# Microcontroller_Power___RF.net
KiCad netlist of a schematic drawn in Altium Designer
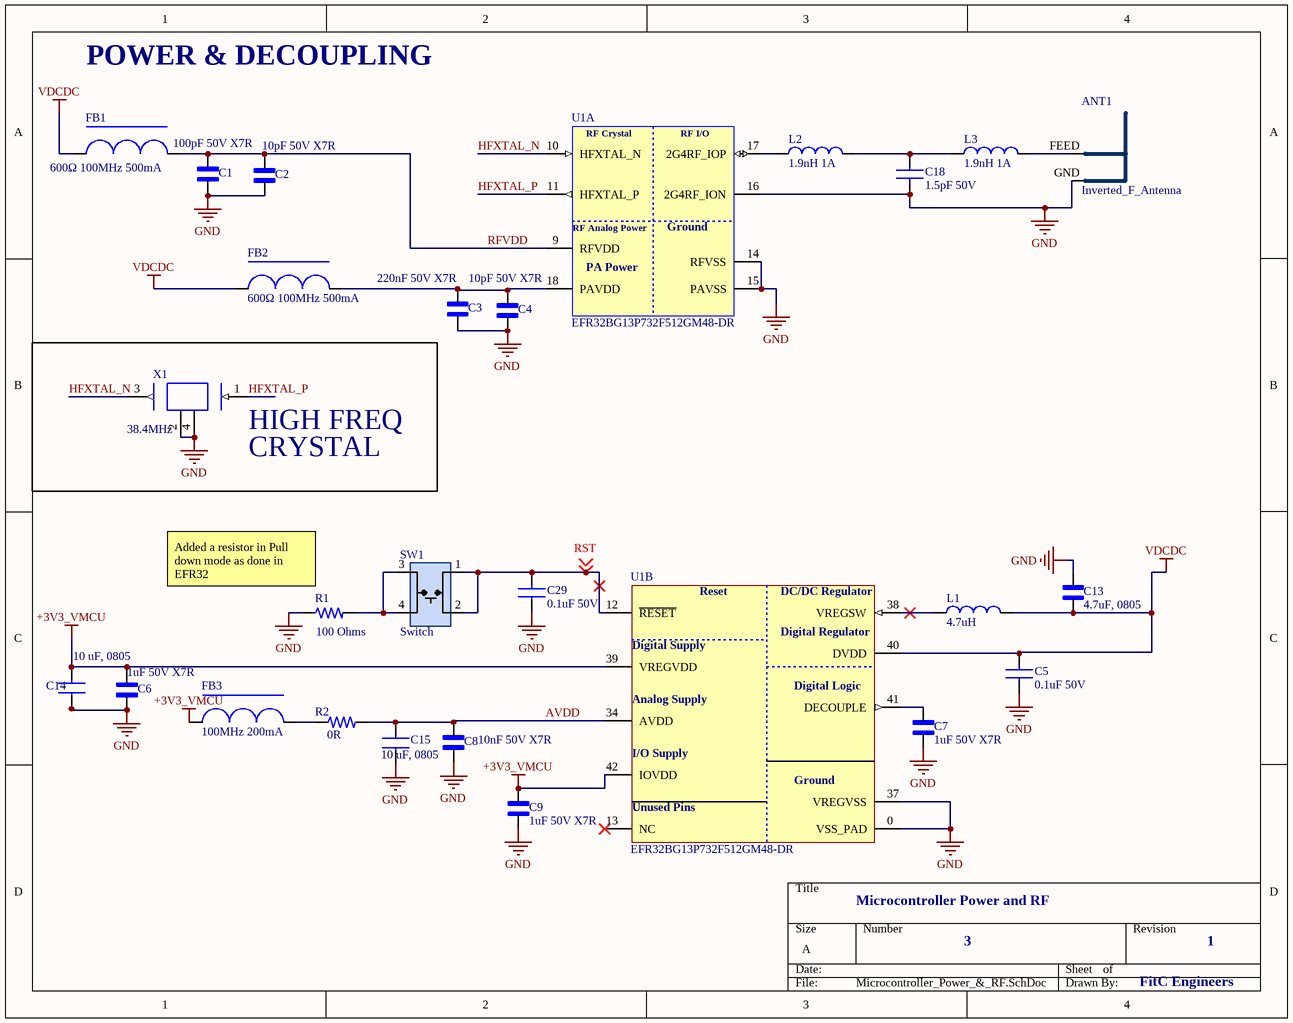
[diagram p0: Microcontroller_Power_&_RF.SchDoc]

(export (version "E")
  (design (tool "Eeschema 10.0.6"))
  (components
    (comp (ref "ANT1")
      (value "Inverted_F_Antenna")
      (footprint "INV_F_Antenna")
      (libsource (lib "LP_Project_Parts") (part "Inv_F_Antenna"))
    )
    (comp (ref "C1")
      (value "100pF 50V X7R")
      (footprint "CAP_0603_1MM")
      (description "100pF ±10% 50V 0603")
      (fields
        (field (name "MANUFACTURER") "Samsung")
        (field (name "MANUFACTURER PART NUMBER") "CL10B101KB8NFNC")
      )
      (libsource (lib "LP_Project_Parts") (part "CL10B101KB8NFNC"))
    )
    (comp (ref "C2")
      (value "10pF 50V X7R")
      (footprint "CAP_0603_1MM")
      (description "0603 10 pF 50 V ±10 % Tolerance X7R Surface Mount Multilayer Ceramic Capacitor")
      (fields
        (field (name "MANUFACTURER") "Kyocera AVX")
        (field (name "MANUFACTURER PART NUMBER") "06035C100KAT2A")
      )
      (libsource (lib "LP_Project_Parts") (part "06035C100KAT2A"))
    )
    (comp (ref "C3")
      (value "220nF 50V X7R")
      (footprint "CAP_0603_1MM")
      (description "C Series 0603 0.22 uF 50 V ±10 % Tolerance X7R SMT Multilayer Ceramic Capacitor")
      (fields
        (field (name "MANUFACTURER") "TDK")
        (field (name "MANUFACTURER PART NUMBER") "C1608X7R1H224K080AB")
      )
      (libsource (lib "LP_Project_Parts") (part "C1608X7R1H224K080AB"))
    )
    (comp (ref "C4")
      (value "10pF 50V X7R")
      (footprint "CAP_0603_1MM")
      (description "0603 10 pF 50 V ±10 % Tolerance X7R Surface Mount Multilayer Ceramic Capacitor")
      (fields
        (field (name "MANUFACTURER") "Kyocera AVX")
        (field (name "MANUFACTURER PART NUMBER") "06035C100KAT2A")
      )
      (libsource (lib "LP_Project_Parts") (part "06035C100KAT2A"))
    )
    (comp (ref "C5")
      (value "0.1uF 50V")
      (footprint "CAP_0603_1MM")
      (description "Cap Ceramic 0.1uF 50V X7R 10% Pad SMD 0603 Flexible Termination 125C Automotive Medical Bag")
      (fields
        (field (name "MANUFACTURER") "KEMET")
        (field (name "MANUFACTURER PART NUMBER") "C0603X104K5RAC3121")
      )
      (libsource (lib "LP_Project_Parts") (part "C0603X104K5RAC3121"))
    )
    (comp (ref "C6")
      (value "1uF 50V X7R")
      (footprint "CAP_0603_1MM")
      (description "0603 1uF Multilayer Ceramic Capacitors 0603 50V X7R 105 10% TOL")
      (fields
        (field (name "MANUFACTURER") "Kyocera AVX")
        (field (name "MANUFACTURER PART NUMBER") "06035C105KAT2A")
      )
      (libsource (lib "LP_Project_Parts") (part "06035C105KAT2A"))
    )
    (comp (ref "C7")
      (value "1uF 50V X7R")
      (footprint "CAP_0603_1MM")
      (description "0603 1uF Multilayer Ceramic Capacitors 0603 50V X7R 105 10% TOL")
      (fields
        (field (name "MANUFACTURER") "Kyocera AVX")
        (field (name "MANUFACTURER PART NUMBER") "06035C105KAT2A")
      )
      (libsource (lib "LP_Project_Parts") (part "06035C105KAT2A"))
    )
    (comp (ref "C8")
      (value "10nF 50V X7R")
      (footprint "CAP_0603_1MM")
      (description "Capacitor Ceramic 0.01uF 10% 50V 2-Pin Surface Mount T/R")
      (fields
        (field (name "MANUFACTURER") "Samsung")
        (field (name "MANUFACTURER PART NUMBER") "CL10B103KB8WPJC")
      )
      (libsource (lib "LP_Project_Parts") (part "CL10B103KB8WPJC"))
    )
    (comp (ref "C9")
      (value "1uF 50V X7R")
      (footprint "CAP_0603_1MM")
      (description "0603 1uF Multilayer Ceramic Capacitors 0603 50V X7R 105 10% TOL")
      (fields
        (field (name "MANUFACTURER") "Kyocera AVX")
        (field (name "MANUFACTURER PART NUMBER") "06035C105KAT2A")
      )
      (libsource (lib "LP_Project_Parts") (part "06035C105KAT2A"))
    )
    (comp (ref "C13")
      (value "4.7uF, 0805")
      (footprint "CAP_0805_2012X14")
      (description "0805 4.7 uF 25 V ±10% Tolerance X5R SMT Multilayer Ceramic Capacitor")
      (fields
        (field (name "MANUFACTURER") "Yageo")
        (field (name "MANUFACTURER PART NUMBER") "CC0805KKX5R8BB475")
      )
      (libsource (lib "LP_Project_Parts") (part "CC0805KKX5R8BB475"))
    )
    (comp (ref "C14")
      (value "10 uF, 0805")
      (footprint "CAP_0805_2012X14")
      (description "0805 25 V 10 uF ±20% Tolerance X5R Monolithic Ceramic Chip Capacitor")
      (fields
        (field (name "MANUFACTURER") "Murata")
        (field (name "MANUFACTURER PART NUMBER") "GRM21BR61E106KA73K")
      )
      (libsource (lib "LP_Project_Parts") (part "GRM21BR61E106KA73K"))
    )
    (comp (ref "C15")
      (value "10 uF, 0805")
      (footprint "CAP_0805_2012X14")
      (description "0805 25 V 10 uF ±20% Tolerance X5R Monolithic Ceramic Chip Capacitor")
      (fields
        (field (name "MANUFACTURER") "Murata")
        (field (name "MANUFACTURER PART NUMBER") "GRM21BR61E106KA73K")
      )
      (libsource (lib "LP_Project_Parts") (part "GRM21BR61E106KA73K"))
    )
    (comp (ref "C18")
      (value "1.5pF 50V")
      (footprint "CAP_0402_1mm")
      (description "Cap Ceramic 1.5pF 50V C0G 5% Pad SMD 0402 125C Automotive T/R")
      (fields
        (field (name "MANUFACTURER") "Murata")
        (field (name "MANUFACTURER PART NUMBER") "GCM1555C1H1R5JA16D")
      )
      (libsource (lib "LP_Project_Parts") (part "GCM1555C1H1R5JA16D"))
    )
    (comp (ref "C29")
      (value "0.1uF 50V")
      (footprint "CAP_0603_1MM")
      (description "Cap Ceramic 0.1uF 50V X7R 10% Pad SMD 0603 Flexible Termination 125C Automotive Medical Bag")
      (fields
        (field (name "MANUFACTURER") "KEMET")
        (field (name "MANUFACTURER PART NUMBER") "C0603X104K5RAC3121")
      )
      (libsource (lib "LP_Project_Parts") (part "C0603X104K5RAC3121"))
    )
    (comp (ref "FB1")
      (value "600Ω 100MHz 500mA")
      (footprint "RES_0603_1608X06")
      (description "0603 600Ω ±25% DCR=0.38Ω 500mA")
      (fields
        (field (name "MANUFACTURER") "Murata")
        (field (name "MANUFACTURER PART NUMBER") "BLM18AG601SN1D")
      )
      (libsource (lib "LP_Project_Parts") (part "BLM18AG601SN1D"))
    )
    (comp (ref "FB2")
      (value "600Ω 100MHz 500mA")
      (footprint "RES_0603_1608X06")
      (description "0603 600Ω ±25% DCR=0.38Ω 500mA")
      (fields
        (field (name "MANUFACTURER") "Murata")
        (field (name "MANUFACTURER PART NUMBER") "BLM18AG601SN1D")
      )
      (libsource (lib "LP_Project_Parts") (part "BLM18AG601SN1D"))
    )
    (comp (ref "FB3")
      (value "100MHz 200mA")
      (footprint "RES_0603_1608X06")
      (description "Ferrite Beads WE-CBF 0603 SMD Bead 100MHz 1000Ohm 200mA")
      (fields
        (field (name "MANUFACTURER") "Wurth Electronics")
        (field (name "MANUFACTURER PART NUMBER") "74279266")
      )
      (libsource (lib "LP_Project_Parts") (part "74279266"))
    )
    (comp (ref "L1")
      (value "4.7uH")
      (footprint "VLS201612CX-100M-1")
      (description "4.7uH Inductor Power Shielded Wirewound  20% 1MHz Ferrite 1.12A 0.252Ohm DCR 0806 T/R")
      (fields
        (field (name "MANUFACTURER") "TDK")
        (field (name "MANUFACTURER PART NUMBER") "VLS201612CX-4R7M-1")
      )
      (libsource (lib "LP_Project_Parts") (part "VLS201612CX-4R7M-1"))
    )
    (comp (ref "L2")
      (value "1.9nH 1A")
      (footprint "CAP_0402_1mm")
      (description "Inductor Chip 1.9nH 0.3nH Tolerance 2-Pin 0402 Paper T/R")
      (fields
        (field (name "MANUFACTURER") "Murata")
        (field (name "MANUFACTURER PART NUMBER") "LQG15WZ1N9S02D")
      )
      (libsource (lib "LP_Project_Parts") (part "LQG15WZ1N9S02D"))
    )
    (comp (ref "L3")
      (value "1.9nH 1A")
      (footprint "CAP_0402_1mm")
      (description "Inductor Chip 1.9nH 0.3nH Tolerance 2-Pin 0402 Paper T/R")
      (fields
        (field (name "MANUFACTURER") "Murata")
        (field (name "MANUFACTURER PART NUMBER") "LQG15WZ1N9S02D")
      )
      (libsource (lib "LP_Project_Parts") (part "LQG15WZ1N9S02D"))
    )
    (comp (ref "R1")
      (value "100 Ohms")
      (footprint "RES_0603_1608X06")
      (description "Res Thin Film 0603 100 Ohm 0.1% 0.1W(1/10W) ±25ppm/C Pad SMD T/R")
      (fields
        (field (name "MANUFACTURER") "Yageo")
        (field (name "MANUFACTURER PART NUMBER") "RT0603BRD07100RL")
      )
      (libsource (lib "LP_Project_Parts") (part "RT0603BRD07100RL"))
    )
    (comp (ref "R2")
      (value "0R")
      (footprint "RES_0603_1608X06")
      (description "Res Thkflm 0603 0 Ohm Jumper 1/10W 100Ppm/ C Smd Rohs Compliant: Yes")
      (fields
        (field (name "MANUFACTURER") "Stackpole Electronics")
        (field (name "MANUFACTURER PART NUMBER") "RMCF0603ZT0R00")
      )
      (libsource (lib "LP_Project_Parts") (part "RMCF0603ZT0R00"))
    )
    (comp (ref "SW1")
      (value "Switch")
      (footprint "SWITCH")
      (description "Switch Tactile SPST-NO Button Gull Wing 50mA 12VDC 100000Cycle 180gf Surface Mount T/R")
      (fields
        (field (name "MANUFACTURER") "C&K Components")
        (field (name "MANUFACTURER PART NUMBER") "RKB2SJM250SMTR LFS")
      )
      (libsource (lib "LP_Project_Parts") (part "RKB2SJM250SMTR LFS (2)"))
    )
    (comp (ref "U1")
      (value "EFR32BG13P732F512GM48-DR")
      (footprint "EFR32BG13_48_QFN")
      (description "Blue Gecko QFN48 2.4 G 19 dB BLE/Proprietary 512 kB 64 kB(RAM) 31GPIO")
      (fields (field (name "MANUFACTURER") "Silicon Labs"))
      (libsource (lib "LP_Project_Parts") (part "EFR32BG13P732F512GM48-DR"))
    )
    (comp (ref "X1")
      (value "38.4MHz")
      (footprint "OSC_38.4MHz")
      (description "Crystal 38.4000MHZ 10PF SMD")
      (fields
        (field (name "MANUFACTURER") "Raltron Electronics")
        (field (name "MANUFACTURER PART NUMBER") "RH100-38.400-10-F-1010-TR")
      )
      (libsource (lib "LP_Project_Parts") (part "RH100-38.400-10-F-1010-TR"))
    )
  )
  (nets
    (net (code "1") (name "+3V3_VMCU") (class "Default")
      (node (ref "C14") (pin "2") (pinfunction "2_2") (pintype "passive"))
      (node (ref "C6") (pin "1") (pinfunction "1_1") (pintype "passive"))
      (node (ref "C9") (pin "1") (pinfunction "1_1") (pintype "passive"))
      (node (ref "FB3") (pin "1") (pinfunction "1_1") (pintype "passive"))
      (node (ref "U1") (pin "39") (pinfunction "VREGVDD_39") (pintype "power_in"))
      (node (ref "U1") (pin "42") (pinfunction "IOVDD_42") (pintype "power_in"))
    )
    (net (code "2") (name "/AVDD") (class "Default")
      (node (ref "C15") (pin "2") (pinfunction "2_2") (pintype "passive"))
      (node (ref "C8") (pin "1") (pinfunction "1_1") (pintype "passive"))
      (node (ref "R2") (pin "2") (pinfunction "2_2") (pintype "passive"))
      (node (ref "U1") (pin "34") (pinfunction "AVDD_34") (pintype "power_in"))
    )
    (net (code "3") (name "/HFXTAL_N") (class "Default")
      (node (ref "U1") (pin "10") (pinfunction "HFXTAL_N_10") (pintype "input"))
      (node (ref "X1") (pin "3") (pintype "output"))
    )
    (net (code "4") (name "/HFXTAL_P") (class "Default")
      (node (ref "U1") (pin "11") (pinfunction "HFXTAL_P_11") (pintype "output"))
      (node (ref "X1") (pin "1") (pintype "input"))
    )
    (net (code "5") (name "/RFVDD") (class "Default")
      (node (ref "C1") (pin "1") (pinfunction "1_1") (pintype "passive"))
      (node (ref "C2") (pin "1") (pinfunction "1_1") (pintype "passive"))
      (node (ref "FB1") (pin "2") (pinfunction "2_2") (pintype "passive"))
      (node (ref "U1") (pin "9") (pinfunction "RFVDD_9") (pintype "power_in"))
    )
    (net (code "6") (name "GND") (class "Default")
      (node (ref "ANT1") (pin "GND") (pinfunction "13_GND") (pintype "passive"))
      (node (ref "C1") (pin "2") (pinfunction "2_2") (pintype "passive"))
      (node (ref "C13") (pin "1") (pinfunction "1_1") (pintype "passive"))
      (node (ref "C14") (pin "1") (pinfunction "1_1") (pintype "passive"))
      (node (ref "C15") (pin "1") (pinfunction "1_1") (pintype "passive"))
      (node (ref "C18") (pin "2") (pinfunction "2_2") (pintype "passive"))
      (node (ref "C2") (pin "2") (pinfunction "2_2") (pintype "passive"))
      (node (ref "C29") (pin "2") (pinfunction "2_2") (pintype "passive"))
      (node (ref "C3") (pin "2") (pinfunction "2_2") (pintype "passive"))
      (node (ref "C4") (pin "2") (pinfunction "2_2") (pintype "passive"))
      (node (ref "C5") (pin "2") (pinfunction "2_2") (pintype "passive"))
      (node (ref "C6") (pin "2") (pinfunction "2_2") (pintype "passive"))
      (node (ref "C7") (pin "2") (pinfunction "2_2") (pintype "passive"))
      (node (ref "C8") (pin "2") (pinfunction "2_2") (pintype "passive"))
      (node (ref "C9") (pin "2") (pinfunction "2_2") (pintype "passive"))
      (node (ref "R1") (pin "1") (pinfunction "1_1") (pintype "passive"))
      (node (ref "U1") (pin "0") (pinfunction "VSS_PAD_0") (pintype "power_in"))
      (node (ref "U1") (pin "14") (pinfunction "RFVSS_14") (pintype "passive"))
      (node (ref "U1") (pin "15") (pinfunction "PAVSS_15") (pintype "passive"))
      (node (ref "U1") (pin "16") (pinfunction "2G4RF_ION_16") (pintype "passive"))
      (node (ref "U1") (pin "37") (pinfunction "VREGVSS_37") (pintype "power_in"))
      (node (ref "X1") (pin "2") (pintype "power_in"))
      (node (ref "X1") (pin "4") (pintype "power_in"))
    )
    (net (code "7") (name "Net-(ANT1-14)") (class "Default")
      (node (ref "ANT1") (pin "FEED") (pinfunction "14_FEED") (pintype "passive"))
      (node (ref "L3") (pin "2") (pinfunction "2_2") (pintype "passive"))
    )
    (net (code "8") (name "Net-(C18-Pad1)") (class "Default")
      (node (ref "C18") (pin "1") (pinfunction "1_1") (pintype "passive"))
      (node (ref "L2") (pin "2") (pinfunction "2_2") (pintype "passive"))
      (node (ref "L3") (pin "1") (pinfunction "1_1") (pintype "passive"))
    )
    (net (code "9") (name "Net-(FB3-Pad2)") (class "Default")
      (node (ref "FB3") (pin "2") (pinfunction "2_2") (pintype "passive"))
      (node (ref "R2") (pin "1") (pinfunction "1_1") (pintype "passive"))
    )
    (net (code "10") (name "Net-(R1-Pad2)") (class "Default")
      (node (ref "R1") (pin "2") (pinfunction "2_2") (pintype "passive"))
      (node (ref "SW1") (pin "3") (pinfunction "3_3") (pintype "passive"))
      (node (ref "SW1") (pin "4") (pinfunction "4_4") (pintype "passive"))
    )
    (net (code "11") (name "Net-(U1A-2G4RF_IOP)") (class "Default")
      (node (ref "L2") (pin "1") (pinfunction "1_1") (pintype "passive"))
      (node (ref "U1") (pin "17") (pinfunction "2G4RF_IOP_17") (pintype "bidirectional"))
    )
    (net (code "12") (name "Net-(U1A-PAVDD)") (class "Default")
      (node (ref "C3") (pin "1") (pinfunction "1_1") (pintype "passive"))
      (node (ref "C4") (pin "1") (pinfunction "1_1") (pintype "passive"))
      (node (ref "FB2") (pin "2") (pinfunction "2_2") (pintype "passive"))
      (node (ref "U1") (pin "18") (pinfunction "PAVDD_18") (pintype "power_in"))
    )
    (net (code "13") (name "Net-(U1B-DECOUPLE)") (class "Default")
      (node (ref "C7") (pin "1") (pinfunction "1_1") (pintype "passive"))
      (node (ref "U1") (pin "41") (pinfunction "DECOUPLE_41") (pintype "output"))
    )
    (net (code "14") (name "Net-(U1B-VREGSW)") (class "Default")
      (node (ref "L1") (pin "1") (pinfunction "1_1") (pintype "passive"))
      (node (ref "U1") (pin "38") (pinfunction "VREGSW_38") (pintype "input"))
    )
    (net (code "15") (name "RST") (class "Default")
      (node (ref "C29") (pin "1") (pinfunction "1_1") (pintype "passive"))
      (node (ref "SW1") (pin "1") (pinfunction "1_1") (pintype "passive"))
      (node (ref "SW1") (pin "2") (pinfunction "2_2") (pintype "passive"))
      (node (ref "U1") (pin "12") (pinfunction "~{RESET}_12") (pintype "passive"))
    )
    (net (code "16") (name "VDCDC") (class "Default")
      (node (ref "C13") (pin "2") (pinfunction "2_2") (pintype "passive"))
      (node (ref "C5") (pin "1") (pinfunction "1_1") (pintype "passive"))
      (node (ref "FB1") (pin "1") (pinfunction "1_1") (pintype "passive"))
      (node (ref "FB2") (pin "1") (pinfunction "1_1") (pintype "passive"))
      (node (ref "L1") (pin "2") (pinfunction "2_2") (pintype "passive"))
      (node (ref "U1") (pin "40") (pinfunction "DVDD_40") (pintype "power_in"))
    )
    (net (code "17") (name "unconnected-(U1B-NC-Pad13)") (class "Default")
      (node (ref "U1") (pin "13") (pinfunction "NC_13") (pintype "passive+no_connect"))
    )
  )
)
